# isolation.net
KiCad netlist of a schematic drawn in EAGLE
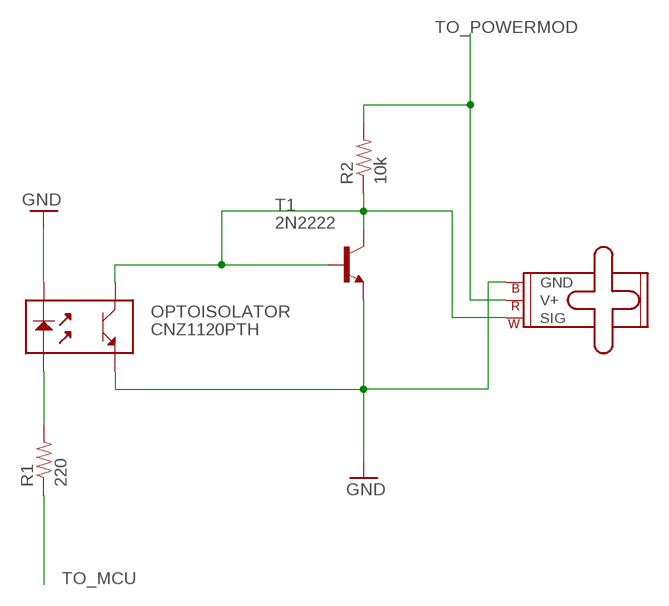
[diagram p0: schematic, sheet 1]

(export (version "E")
  (design (tool "Eeschema 10.0.6"))
  (components
    (comp (ref "M1")
      (value "SMALL_SERVO")
      (footprint "eagle-import:1X03")
      (libsource (lib "eagle-import") (part "SMALL_SERVO"))
    )
    (comp (ref "OPTOISOLATOR")
      (value "CNZ1120PTH")
      (footprint "eagle-import:CNZ1120")
      (libsource (lib "eagle-import") (part "CNZ1120PTH"))
    )
    (comp (ref "R1")
      (value "220")
      (footprint "eagle-import:AXIAL-0.3EZ")
      (libsource (lib "eagle-import") (part "RESISTOREZ"))
    )
    (comp (ref "R2")
      (value "10k")
      (footprint "eagle-import:AXIAL-0.3EZ")
      (libsource (lib "eagle-import") (part "RESISTOREZ"))
    )
    (comp (ref "T1")
      (value "2N2222")
      (footprint "eagle-import:TO92-EBC-OVAL")
      (libsource (lib "eagle-import") (part "2N2222"))
    )
  )
  (nets
    (net (code "1") (name "/TO_MCU") (class "Default")
      (node (ref "R1") (pin "P$1") (pinfunction "1_P$1") (pintype "passive"))
    )
    (net (code "2") (name "/TO_POWERMOD") (class "Default")
      (node (ref "M1") (pin "2") (pinfunction "V+_2") (pintype "bidirectional"))
      (node (ref "R2") (pin "P$2") (pinfunction "2_P$2") (pintype "passive"))
    )
    (net (code "3") (name "GND") (class "Default")
      (node (ref "M1") (pin "3") (pinfunction "GND_3") (pintype "bidirectional"))
      (node (ref "OPTOISOLATOR") (pin "2") (pinfunction "2_2") (pintype "bidirectional"))
      (node (ref "OPTOISOLATOR") (pin "4") (pinfunction "4_4") (pintype "bidirectional"))
      (node (ref "T1") (pin "E") (pinfunction "E_E") (pintype "passive"))
    )
    (net (code "4") (name "Net-(M1-SIG)") (class "Default")
      (node (ref "M1") (pin "1") (pinfunction "SIG_1") (pintype "bidirectional"))
      (node (ref "OPTOISOLATOR") (pin "3") (pinfunction "3_3") (pintype "bidirectional"))
      (node (ref "R2") (pin "P$1") (pinfunction "1_P$1") (pintype "passive"))
      (node (ref "T1") (pin "B") (pinfunction "B_B") (pintype "passive"))
      (node (ref "T1") (pin "C") (pinfunction "C_C") (pintype "passive"))
    )
    (net (code "5") (name "Net-(R1-2)") (class "Default")
      (node (ref "OPTOISOLATOR") (pin "1") (pinfunction "1_1") (pintype "bidirectional"))
      (node (ref "R1") (pin "P$2") (pinfunction "2_P$2") (pintype "passive"))
    )
  )
)
